# smd_challenge_extreme.net
KiCad netlist of a schematic drawn in Altium Designer
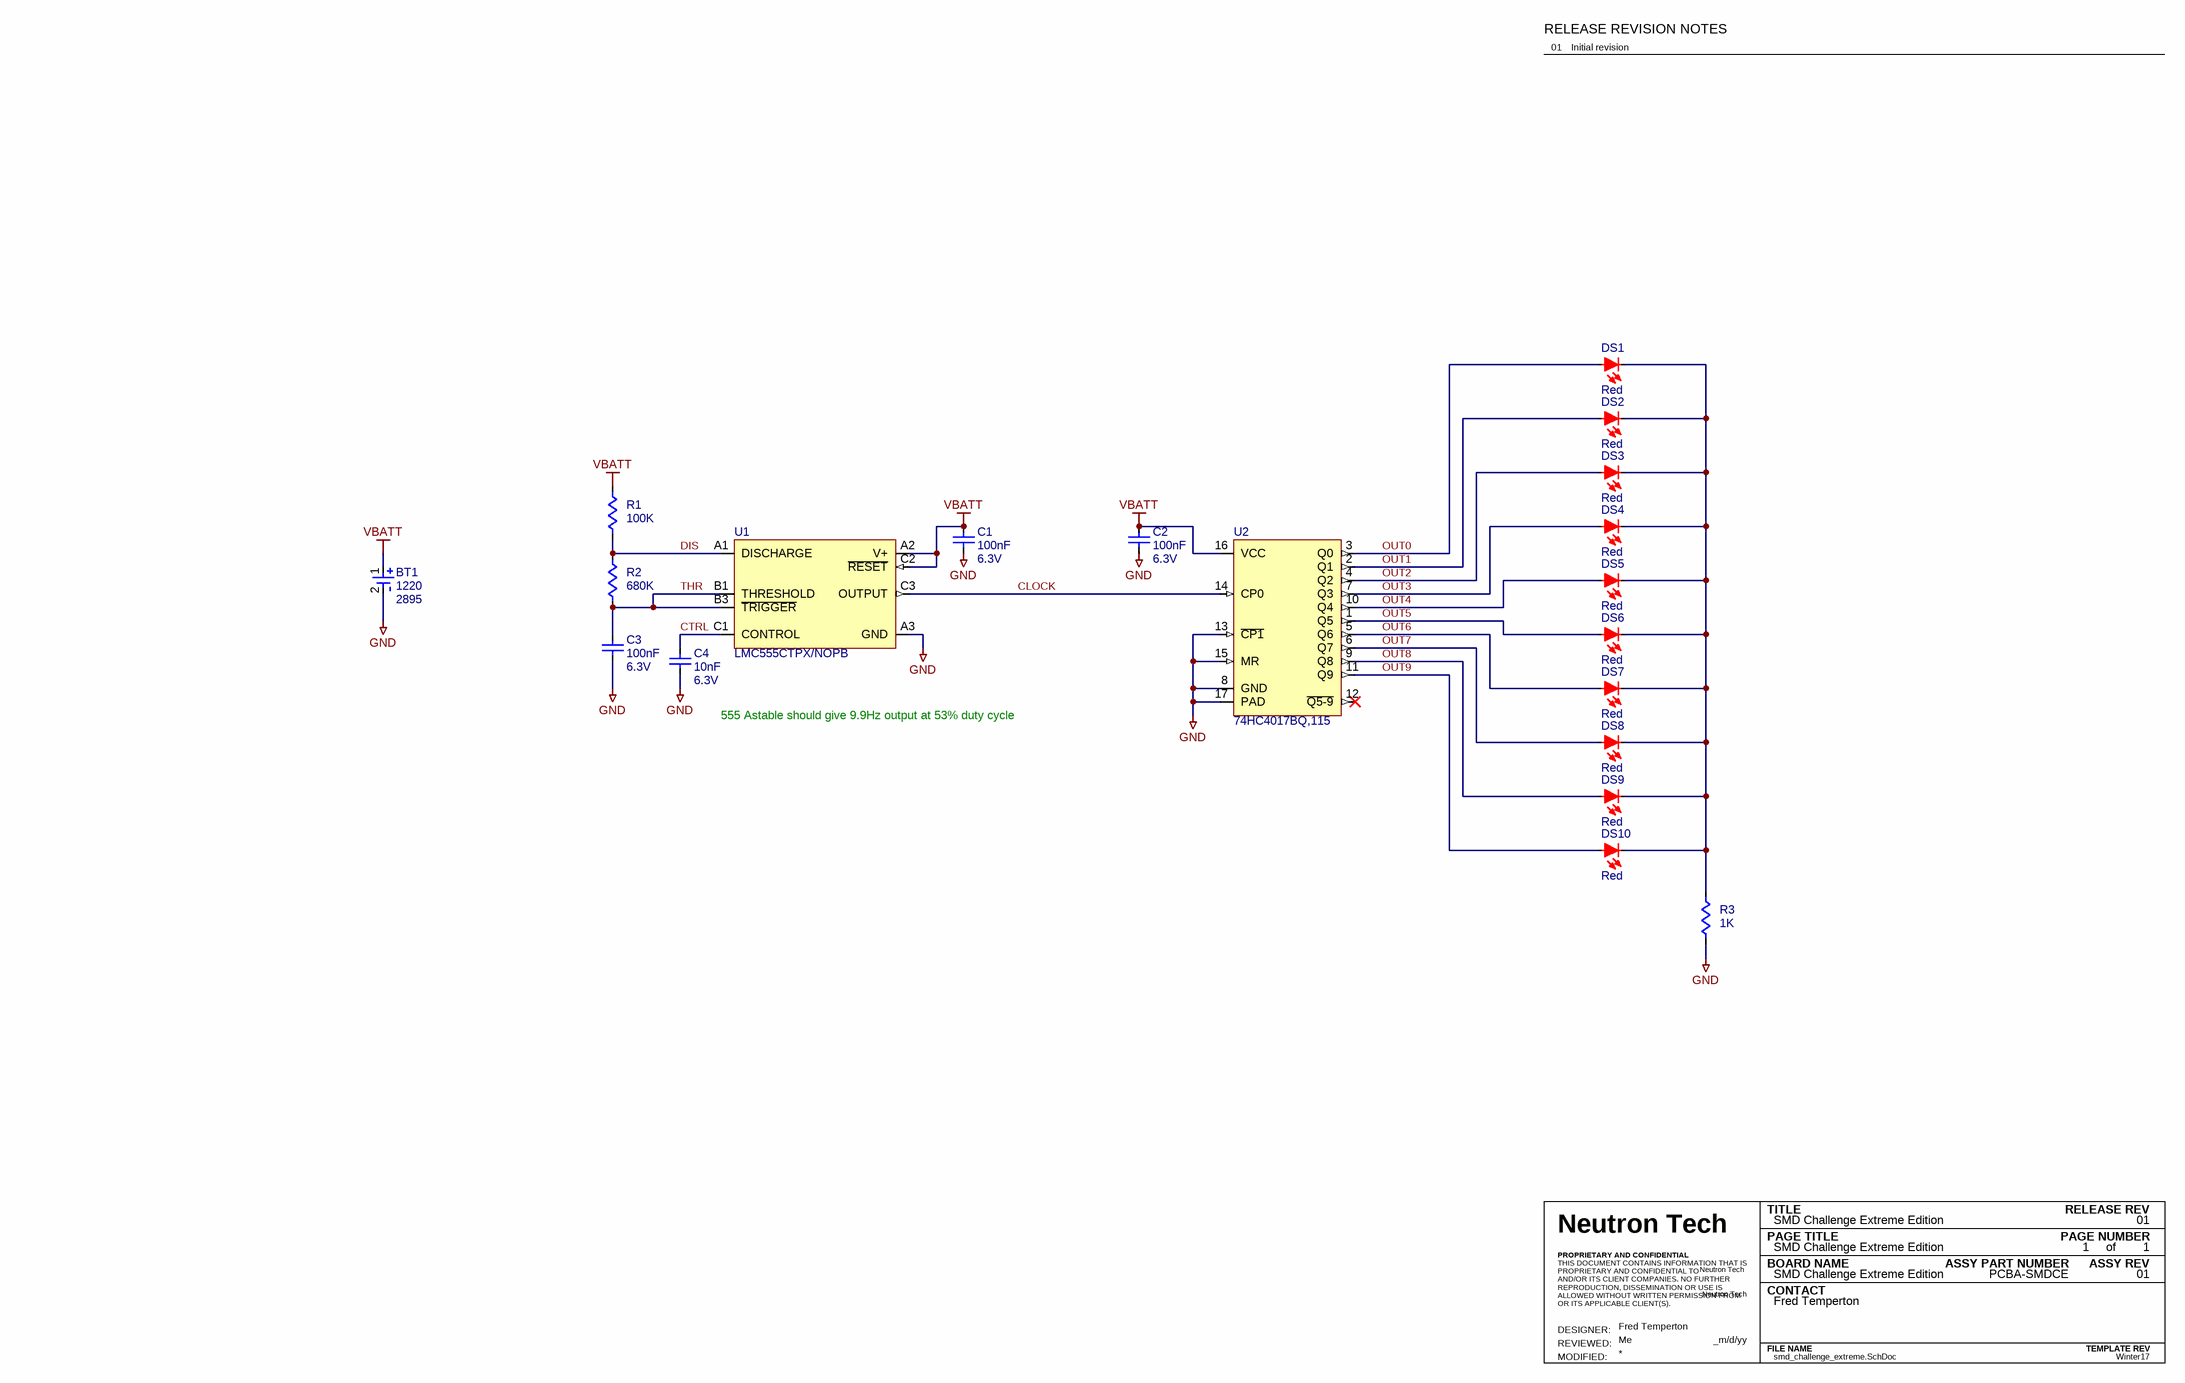
[diagram p0: smd_challenge_extreme.SchDoc]

(export (version "E")
  (design (tool "Eeschema 10.0.6"))
  (components
    (comp (ref "BT1")
      (value "?")
      (footprint "BATT1220-KEYSTONE2895")
      (description "CR1220 COIN CELL THM RETAINER")
      (fields
        (field (name "SIZE") "1220")
        (field (name "MANUFACTURER PART NUMBER 1") "2895")
        (field (name "_VERIFIED BOM") ".mfr-pn?")
        (field (name "_VERIFIED FOOTPRINT") ".mfr-pn? footprint?")
        (field (name "_VERIFIED SYMBOL") ".mfr-pn?")
      )
      (libsource (lib "smd_challenge_extreme") (part "BAT CELL HOLDER 1220"))
    )
    (comp (ref "C1")
      (value "?")
      (footprint "CAPC0402X02N")
      (description "CAP CER 0.1UF 6.3V X5R 01005")
      (fields
        (field (name "VOLTAGE 1") "6.3V")
        (field (name "CAPACITANCE 1") "100nF")
        (field (name "_VERIFIED FOOTPRINT") ".mfr-pn? footprint?")
        (field (name "_VERIFIED BOM") ".mfr-pn?")
        (field (name "_VERIFIED SYMBOL") ".mfr-pn?")
      )
      (libsource (lib "smd_challenge_extreme") (part "CAP 100nF 01005"))
    )
    (comp (ref "C2")
      (value "?")
      (footprint "CAPC0402X02N")
      (description "CAP CER 0.1UF 6.3V X5R 01005")
      (fields
        (field (name "VOLTAGE 1") "6.3V")
        (field (name "CAPACITANCE 1") "100nF")
        (field (name "_VERIFIED FOOTPRINT") ".mfr-pn? footprint?")
        (field (name "_VERIFIED BOM") ".mfr-pn?")
        (field (name "_VERIFIED SYMBOL") ".mfr-pn?")
      )
      (libsource (lib "smd_challenge_extreme") (part "CAP 100nF 01005"))
    )
    (comp (ref "C3")
      (value "?")
      (footprint "CAPC0402X02N")
      (description "CAP CER 0.1UF 6.3V X5R 01005")
      (fields
        (field (name "VOLTAGE 1") "6.3V")
        (field (name "CAPACITANCE 1") "100nF")
        (field (name "_VERIFIED FOOTPRINT") ".mfr-pn? footprint?")
        (field (name "_VERIFIED BOM") ".mfr-pn?")
        (field (name "_VERIFIED SYMBOL") ".mfr-pn?")
      )
      (libsource (lib "smd_challenge_extreme") (part "CAP 100nF 01005"))
    )
    (comp (ref "C4")
      (value "?")
      (footprint "CAPC0402X02N")
      (description "CAP CER 10000PF 6.3V X7S 01005")
      (fields
        (field (name "VOTLAGE 1") "6.3V")
        (field (name "CAPACITANCE 1") "10nF")
        (field (name "_VERIFIED FOOTPRINT") ".mfr-pn? footprint?")
        (field (name "_VERIFIED BOM") ".mfr-pn?")
        (field (name "_VERIFIED SYMBOL") ".mfr-pn?")
      )
      (libsource (lib "smd_challenge_extreme") (part "CAP 10nF 01005"))
    )
    (comp (ref "DS1")
      (value "?")
      (footprint "DIOC0604X02N")
      (description "LED RED CLEAR 2SMD")
      (fields
        (field (name "COLOUR") "Red")
        (field (name "_VERIFIED FOOTPRINT") ".mfr-pn? footprint?")
        (field (name "_VERIFIED BOM") ".mfr-pn?")
        (field (name "_VERIFIED SYMBOL") ".mfr-pn?")
      )
      (libsource (lib "smd_challenge_extreme") (part "LED RED 0201"))
    )
    (comp (ref "DS2")
      (value "?")
      (footprint "DIOC0604X02N")
      (description "LED RED CLEAR 2SMD")
      (fields
        (field (name "COLOUR") "Red")
        (field (name "_VERIFIED FOOTPRINT") ".mfr-pn? footprint?")
        (field (name "_VERIFIED BOM") ".mfr-pn?")
        (field (name "_VERIFIED SYMBOL") ".mfr-pn?")
      )
      (libsource (lib "smd_challenge_extreme") (part "LED RED 0201"))
    )
    (comp (ref "DS3")
      (value "?")
      (footprint "DIOC0604X02N")
      (description "LED RED CLEAR 2SMD")
      (fields
        (field (name "COLOUR") "Red")
        (field (name "_VERIFIED FOOTPRINT") ".mfr-pn? footprint?")
        (field (name "_VERIFIED BOM") ".mfr-pn?")
        (field (name "_VERIFIED SYMBOL") ".mfr-pn?")
      )
      (libsource (lib "smd_challenge_extreme") (part "LED RED 0201"))
    )
    (comp (ref "DS4")
      (value "?")
      (footprint "DIOC0604X02N")
      (description "LED RED CLEAR 2SMD")
      (fields
        (field (name "COLOUR") "Red")
        (field (name "_VERIFIED FOOTPRINT") ".mfr-pn? footprint?")
        (field (name "_VERIFIED BOM") ".mfr-pn?")
        (field (name "_VERIFIED SYMBOL") ".mfr-pn?")
      )
      (libsource (lib "smd_challenge_extreme") (part "LED RED 0201"))
    )
    (comp (ref "DS5")
      (value "?")
      (footprint "DIOC0604X02N")
      (description "LED RED CLEAR 2SMD")
      (fields
        (field (name "COLOUR") "Red")
        (field (name "_VERIFIED FOOTPRINT") ".mfr-pn? footprint?")
        (field (name "_VERIFIED BOM") ".mfr-pn?")
        (field (name "_VERIFIED SYMBOL") ".mfr-pn?")
      )
      (libsource (lib "smd_challenge_extreme") (part "LED RED 0201"))
    )
    (comp (ref "DS6")
      (value "?")
      (footprint "DIOC0604X02N")
      (description "LED RED CLEAR 2SMD")
      (fields
        (field (name "COLOUR") "Red")
        (field (name "_VERIFIED FOOTPRINT") ".mfr-pn? footprint?")
        (field (name "_VERIFIED BOM") ".mfr-pn?")
        (field (name "_VERIFIED SYMBOL") ".mfr-pn?")
      )
      (libsource (lib "smd_challenge_extreme") (part "LED RED 0201"))
    )
    (comp (ref "DS7")
      (value "?")
      (footprint "DIOC0604X02N")
      (description "LED RED CLEAR 2SMD")
      (fields
        (field (name "COLOUR") "Red")
        (field (name "_VERIFIED FOOTPRINT") ".mfr-pn? footprint?")
        (field (name "_VERIFIED BOM") ".mfr-pn?")
        (field (name "_VERIFIED SYMBOL") ".mfr-pn?")
      )
      (libsource (lib "smd_challenge_extreme") (part "LED RED 0201"))
    )
    (comp (ref "DS8")
      (value "?")
      (footprint "DIOC0604X02N")
      (description "LED RED CLEAR 2SMD")
      (fields
        (field (name "COLOUR") "Red")
        (field (name "_VERIFIED FOOTPRINT") ".mfr-pn? footprint?")
        (field (name "_VERIFIED BOM") ".mfr-pn?")
        (field (name "_VERIFIED SYMBOL") ".mfr-pn?")
      )
      (libsource (lib "smd_challenge_extreme") (part "LED RED 0201"))
    )
    (comp (ref "DS9")
      (value "?")
      (footprint "DIOC0604X02N")
      (description "LED RED CLEAR 2SMD")
      (fields
        (field (name "COLOUR") "Red")
        (field (name "_VERIFIED FOOTPRINT") ".mfr-pn? footprint?")
        (field (name "_VERIFIED BOM") ".mfr-pn?")
        (field (name "_VERIFIED SYMBOL") ".mfr-pn?")
      )
      (libsource (lib "smd_challenge_extreme") (part "LED RED 0201"))
    )
    (comp (ref "DS10")
      (value "?")
      (footprint "DIOC0604X02N")
      (description "LED RED CLEAR 2SMD")
      (fields
        (field (name "COLOUR") "Red")
        (field (name "_VERIFIED FOOTPRINT") ".mfr-pn? footprint?")
        (field (name "_VERIFIED BOM") ".mfr-pn?")
        (field (name "_VERIFIED SYMBOL") ".mfr-pn?")
      )
      (libsource (lib "smd_challenge_extreme") (part "LED RED 0201"))
    )
    (comp (ref "R1")
      (value "?")
      (footprint "RESC0402X01N")
      (description "RES SMD 100K OHM 1% 1/32W 01005")
      (fields
        (field (name "RESISTANCE 1") "100K")
        (field (name "_VERIFIED FOOTPRINT") ".mfr-pn? footprint?")
        (field (name "_VERIFIED BOM") ".mfr-pn?")
        (field (name "_VERIFIED SYMBOL") ".mfr-pn?")
      )
      (libsource (lib "smd_challenge_extreme") (part "RES 100K 01005"))
    )
    (comp (ref "R2")
      (value "?")
      (footprint "RESC0402X01N")
      (description "RES SMD 680K OHM 5% 1/32W 01005")
      (fields
        (field (name "RESISTANCE 1") "680K")
        (field (name "_VERIFIED FOOTPRINT") ".mfr-pn? footprint?")
        (field (name "_VERIFIED BOM") ".mfr-pn?")
        (field (name "_VERIFIED SYMBOL") ".mfr-pn?")
      )
      (libsource (lib "smd_challenge_extreme") (part "RES 680K 01005"))
    )
    (comp (ref "R3")
      (value "?")
      (footprint "RESC0402X01N")
      (description "RES SMD 1K OHM 1% 1/32W 01005")
      (fields
        (field (name "RESISTANCE 1") "1K")
        (field (name "_VERIFIED FOOTPRINT") ".mfr-pn? footprint?")
        (field (name "_VERIFIED BOM") ".mfr-pn?")
        (field (name "_VERIFIED SYMBOL") ".mfr-pn?")
      )
      (libsource (lib "smd_challenge_extreme") (part "RES 1K 01005"))
    )
    (comp (ref "U1")
      (value "?")
      (footprint "BGA8C50P3X3_141X143X57")
      (description "IC OSC SINGLE TIMER 3MHZ 8-USMD")
      (fields
        (field (name "MANUFACTURER PART NUMBER 1") "LMC555CTPX/NOPB")
        (field (name "_VERIFIED FOOTPRINT") ".mfr-pn? footprint?")
        (field (name "_VERIFIED BOM") ".mfr-pn?")
        (field (name "_VERIFIED SYMBOL") ".mfr-pn?")
      )
      (libsource (lib "smd_challenge_extreme") (part "IC LMC555CTPX"))
    )
    (comp (ref "U2")
      (value "?")
      (footprint "QFN50P250X350X100_HS-17N")
      (description "IC JOHNSON DECADE CNTR 16-DHVQFN")
      (fields
        (field (name "MANUFACTURER PART NUMBER 1") "74HC4017BQ,115")
        (field (name "_VERIFIED FOOTPRINT") ".mfr-pn? footprint?")
        (field (name "_VERIFIED BOM") ".mfr-pn?")
        (field (name "_VERIFIED SYMBOL") ".mfr-pn?")
      )
      (libsource (lib "smd_challenge_extreme") (part "IC 74HC4017BQ"))
    )
  )
  (nets
    (net (code "1") (name "/CLOCK") (class "Default")
      (node (ref "U1") (pin "C3") (pinfunction "OUTPUT_C3") (pintype "output"))
      (node (ref "U2") (pin "14") (pinfunction "CP0_14") (pintype "input"))
    )
    (net (code "2") (name "/CTRL") (class "Default")
      (node (ref "C4") (pin "1") (pinfunction "1_1") (pintype "passive"))
      (node (ref "U1") (pin "C1") (pinfunction "CONTROL_C1") (pintype "passive"))
    )
    (net (code "3") (name "/DIS") (class "Default")
      (node (ref "R1") (pin "2") (pinfunction "2_2") (pintype "passive"))
      (node (ref "R2") (pin "1") (pinfunction "1_1") (pintype "passive"))
      (node (ref "U1") (pin "A1") (pinfunction "DISCHARGE_A1") (pintype "passive"))
    )
    (net (code "4") (name "/OUT0") (class "Default")
      (node (ref "DS1") (pin "2") (pinfunction "Anode_2") (pintype "passive"))
      (node (ref "U2") (pin "3") (pinfunction "Q0_3") (pintype "output"))
    )
    (net (code "5") (name "/OUT1") (class "Default")
      (node (ref "DS2") (pin "2") (pinfunction "Anode_2") (pintype "passive"))
      (node (ref "U2") (pin "2") (pinfunction "Q1_2") (pintype "output"))
    )
    (net (code "6") (name "/OUT2") (class "Default")
      (node (ref "DS3") (pin "2") (pinfunction "Anode_2") (pintype "passive"))
      (node (ref "U2") (pin "4") (pinfunction "Q2_4") (pintype "output"))
    )
    (net (code "7") (name "/OUT3") (class "Default")
      (node (ref "DS4") (pin "2") (pinfunction "Anode_2") (pintype "passive"))
      (node (ref "U2") (pin "7") (pinfunction "Q3_7") (pintype "output"))
    )
    (net (code "8") (name "/OUT4") (class "Default")
      (node (ref "DS5") (pin "2") (pinfunction "Anode_2") (pintype "passive"))
      (node (ref "U2") (pin "10") (pinfunction "Q4_10") (pintype "output"))
    )
    (net (code "9") (name "/OUT5") (class "Default")
      (node (ref "DS6") (pin "2") (pinfunction "Anode_2") (pintype "passive"))
      (node (ref "U2") (pin "1") (pinfunction "Q5_1") (pintype "output"))
    )
    (net (code "10") (name "/OUT6") (class "Default")
      (node (ref "DS7") (pin "2") (pinfunction "Anode_2") (pintype "passive"))
      (node (ref "U2") (pin "5") (pinfunction "Q6_5") (pintype "output"))
    )
    (net (code "11") (name "/OUT7") (class "Default")
      (node (ref "DS8") (pin "2") (pinfunction "Anode_2") (pintype "passive"))
      (node (ref "U2") (pin "6") (pinfunction "Q7_6") (pintype "output"))
    )
    (net (code "12") (name "/OUT8") (class "Default")
      (node (ref "DS9") (pin "2") (pinfunction "Anode_2") (pintype "passive"))
      (node (ref "U2") (pin "9") (pinfunction "Q8_9") (pintype "output"))
    )
    (net (code "13") (name "/OUT9") (class "Default")
      (node (ref "DS10") (pin "2") (pinfunction "Anode_2") (pintype "passive"))
      (node (ref "U2") (pin "11") (pinfunction "Q9_11") (pintype "output"))
    )
    (net (code "14") (name "/THR") (class "Default")
      (node (ref "C3") (pin "1") (pinfunction "1_1") (pintype "passive"))
      (node (ref "R2") (pin "2") (pinfunction "2_2") (pintype "passive"))
      (node (ref "U1") (pin "B1") (pinfunction "THRESHOLD_B1") (pintype "passive"))
      (node (ref "U1") (pin "B3") (pinfunction "~{TRIGGER}_B3") (pintype "passive"))
    )
    (net (code "15") (name "GND") (class "Default")
      (node (ref "BT1") (pin "2") (pinfunction "-_2") (pintype "power_in"))
      (node (ref "C1") (pin "2") (pinfunction "2_2") (pintype "passive"))
      (node (ref "C2") (pin "2") (pinfunction "2_2") (pintype "passive"))
      (node (ref "C3") (pin "2") (pinfunction "2_2") (pintype "passive"))
      (node (ref "C4") (pin "2") (pinfunction "2_2") (pintype "passive"))
      (node (ref "R3") (pin "2") (pinfunction "2_2") (pintype "passive"))
      (node (ref "U1") (pin "A3") (pinfunction "GND_A3") (pintype "power_in"))
      (node (ref "U2") (pin "13") (pinfunction "~{CP1}_13") (pintype "input"))
      (node (ref "U2") (pin "15") (pinfunction "MR_15") (pintype "input"))
      (node (ref "U2") (pin "17") (pinfunction "PAD_17") (pintype "power_in"))
      (node (ref "U2") (pin "8") (pinfunction "GND_8") (pintype "power_in"))
    )
    (net (code "16") (name "Net-(DS1-Cathode)") (class "Default")
      (node (ref "DS1") (pin "1") (pinfunction "Cathode_1") (pintype "passive"))
      (node (ref "DS10") (pin "1") (pinfunction "Cathode_1") (pintype "passive"))
      (node (ref "DS2") (pin "1") (pinfunction "Cathode_1") (pintype "passive"))
      (node (ref "DS3") (pin "1") (pinfunction "Cathode_1") (pintype "passive"))
      (node (ref "DS4") (pin "1") (pinfunction "Cathode_1") (pintype "passive"))
      (node (ref "DS5") (pin "1") (pinfunction "Cathode_1") (pintype "passive"))
      (node (ref "DS6") (pin "1") (pinfunction "Cathode_1") (pintype "passive"))
      (node (ref "DS7") (pin "1") (pinfunction "Cathode_1") (pintype "passive"))
      (node (ref "DS8") (pin "1") (pinfunction "Cathode_1") (pintype "passive"))
      (node (ref "DS9") (pin "1") (pinfunction "Cathode_1") (pintype "passive"))
      (node (ref "R3") (pin "1") (pinfunction "1_1") (pintype "passive"))
    )
    (net (code "17") (name "VBATT") (class "Default")
      (node (ref "BT1") (pin "1") (pinfunction "+_1") (pintype "power_in"))
      (node (ref "C1") (pin "1") (pinfunction "1_1") (pintype "passive"))
      (node (ref "C2") (pin "1") (pinfunction "1_1") (pintype "passive"))
      (node (ref "R1") (pin "1") (pinfunction "1_1") (pintype "passive"))
      (node (ref "U1") (pin "A2") (pinfunction "V+_A2") (pintype "power_in"))
      (node (ref "U1") (pin "C2") (pinfunction "~{RESET}_C2") (pintype "input"))
      (node (ref "U2") (pin "16") (pinfunction "VCC_16") (pintype "power_in"))
    )
    (net (code "18") (name "unconnected-(U2-~{Q5-9}-Pad12)") (class "Default")
      (node (ref "U2") (pin "12") (pinfunction "~{Q5-9}_12") (pintype "output+no_connect"))
    )
  )
)
